# kijek_d1.net
KiCad netlist of a schematic drawn in Altium Designer
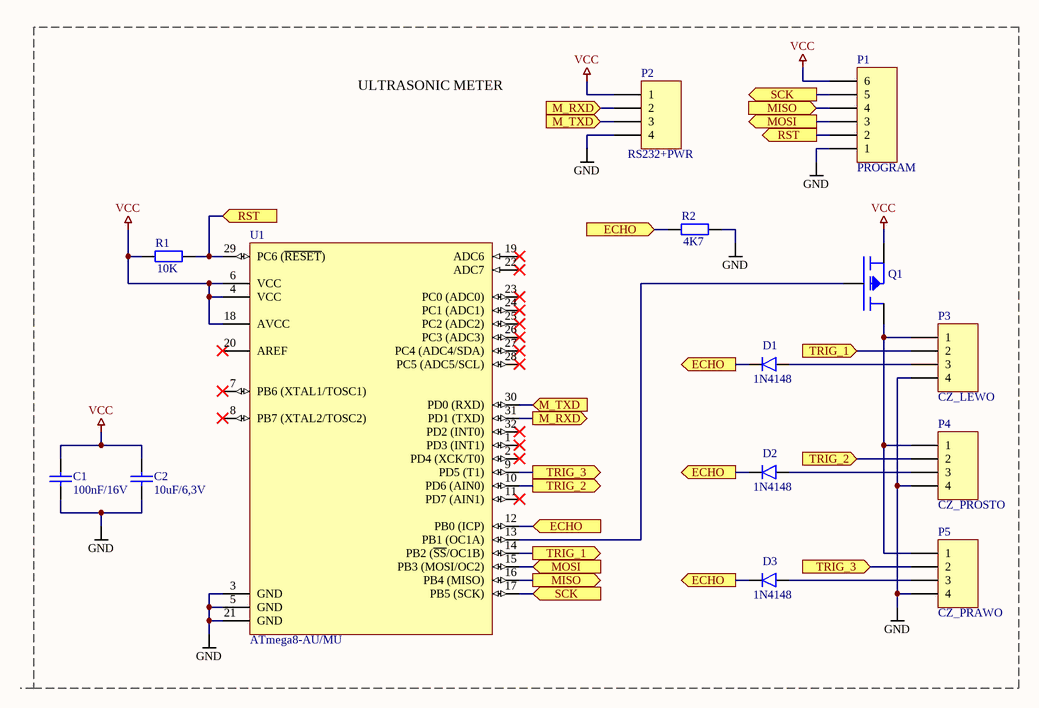
[diagram p0: kijek_d1.SchDoc]

(export (version "E")
  (design (tool "Eeschema 10.0.6"))
  (components
    (comp (ref "C1")
      (value "100nF/16V")
      (footprint "C0402")
      (description "Capacitor")
      (libsource (lib "Library") (part "Cap"))
    )
    (comp (ref "C2")
      (value "10uF/6,3V")
      (footprint "C0603")
      (description "Capacitor")
      (libsource (lib "Library") (part "Cap"))
    )
    (comp (ref "D1") (value "1N4148") (footprint "DO-213A") (libsource (lib "Library") (part "Diode")))
    (comp (ref "D2") (value "1N4148") (footprint "DO-213A") (libsource (lib "Library") (part "Diode")))
    (comp (ref "D3") (value "1N4148") (footprint "DO-213A") (libsource (lib "Library") (part "Diode")))
    (comp (ref "P1")
      (value "PROGRAM")
      (footprint "SMA06-1")
      (description "Header, 6-Pin")
      (libsource (lib "Connectors") (part "Header 6"))
    )
    (comp (ref "P2")
      (value "RS232+PWR")
      (footprint "MA04-1")
      (description "Header, 4-Pin")
      (libsource (lib "Connectors") (part "Header 4"))
    )
    (comp (ref "P3")
      (value "CZ_LEWO")
      (footprint "MA04-1")
      (description "Header, 4-Pin")
      (libsource (lib "Connectors") (part "Header 4"))
    )
    (comp (ref "P4")
      (value "CZ_PROSTO")
      (footprint "MA04-1")
      (description "Header, 4-Pin")
      (libsource (lib "Connectors") (part "Header 4"))
    )
    (comp (ref "P5")
      (value "CZ_PRAWO")
      (footprint "MA04-1")
      (description "Header, 4-Pin")
      (libsource (lib "Connectors") (part "Header 4"))
    )
    (comp (ref "Q1") (value "AO3401") (footprint "SOT23") (libsource (lib "Library") (part "AO3401")))
    (comp (ref "R1")
      (value "10K")
      (footprint "R0402")
      (description "Resistor")
      (libsource (lib "Library") (part "Res"))
    )
    (comp (ref "R2")
      (value "4K7")
      (footprint "R0402")
      (description "Resistor")
      (libsource (lib "Library") (part "Res"))
    )
    (comp (ref "U1")
      (value "ATmega8-AU/MU")
      (footprint "TQFP-32A")
      (description "TQFP - 32pin / MLF - 32pin")
      (libsource (lib "IC") (part "ATmega8-AU/MU"))
    )
  )
  (nets
    (net (code "1") (name "/ECHO") (class "Default")
      (node (ref "D1") (pin "1") (pinfunction "1_1") (pintype "power_in"))
      (node (ref "D2") (pin "1") (pinfunction "1_1") (pintype "power_in"))
      (node (ref "D3") (pin "1") (pinfunction "1_1") (pintype "power_in"))
      (node (ref "R2") (pin "1") (pinfunction "1_1") (pintype "passive"))
      (node (ref "U1") (pin "12") (pinfunction "PB0_(ICP)_12") (pintype "bidirectional"))
    )
    (net (code "2") (name "/MISO") (class "Default")
      (node (ref "P1") (pin "4") (pinfunction "4_4") (pintype "passive"))
      (node (ref "U1") (pin "16") (pinfunction "PB4_(MISO)_16") (pintype "bidirectional"))
    )
    (net (code "3") (name "/MOSI") (class "Default")
      (node (ref "P1") (pin "3") (pinfunction "3_3") (pintype "passive"))
      (node (ref "U1") (pin "15") (pinfunction "PB3_(MOSI/OC2)_15") (pintype "bidirectional"))
    )
    (net (code "4") (name "/M_RXD") (class "Default")
      (node (ref "P2") (pin "2") (pinfunction "2_2") (pintype "passive"))
      (node (ref "U1") (pin "31") (pinfunction "PD1_(TXD)_31") (pintype "bidirectional"))
    )
    (net (code "5") (name "/M_TXD") (class "Default")
      (node (ref "P2") (pin "3") (pinfunction "3_3") (pintype "passive"))
      (node (ref "U1") (pin "30") (pinfunction "PD0_(RXD)_30") (pintype "bidirectional"))
    )
    (net (code "6") (name "/RST") (class "Default")
      (node (ref "P1") (pin "2") (pinfunction "2_2") (pintype "passive"))
      (node (ref "R1") (pin "2") (pinfunction "2_2") (pintype "passive"))
      (node (ref "U1") (pin "29") (pinfunction "PC6_(~{RESET})_29") (pintype "bidirectional"))
    )
    (net (code "7") (name "/SCK") (class "Default")
      (node (ref "P1") (pin "5") (pinfunction "5_5") (pintype "passive"))
      (node (ref "U1") (pin "17") (pinfunction "PB5_(SCK)_17") (pintype "bidirectional"))
    )
    (net (code "8") (name "/TRIG_1") (class "Default")
      (node (ref "P3") (pin "2") (pinfunction "2_2") (pintype "passive"))
      (node (ref "U1") (pin "14") (pinfunction "PB2_(~{SS}/OC1B)_14") (pintype "bidirectional"))
    )
    (net (code "9") (name "/TRIG_2") (class "Default")
      (node (ref "P4") (pin "2") (pinfunction "2_2") (pintype "passive"))
      (node (ref "U1") (pin "10") (pinfunction "PD6_(AIN0)_10") (pintype "bidirectional"))
    )
    (net (code "10") (name "/TRIG_3") (class "Default")
      (node (ref "P5") (pin "2") (pinfunction "2_2") (pintype "passive"))
      (node (ref "U1") (pin "9") (pinfunction "PD5_(T1)_9") (pintype "bidirectional"))
    )
    (net (code "11") (name "GND") (class "Default")
      (node (ref "C1") (pin "2") (pinfunction "2_2") (pintype "passive"))
      (node (ref "C2") (pin "2") (pinfunction "2_2") (pintype "passive"))
      (node (ref "P1") (pin "1") (pinfunction "1_1") (pintype "passive"))
      (node (ref "P2") (pin "4") (pinfunction "4_4") (pintype "passive"))
      (node (ref "P3") (pin "4") (pinfunction "4_4") (pintype "passive"))
      (node (ref "P4") (pin "4") (pinfunction "4_4") (pintype "passive"))
      (node (ref "P5") (pin "4") (pinfunction "4_4") (pintype "passive"))
      (node (ref "R2") (pin "2") (pinfunction "2_2") (pintype "passive"))
      (node (ref "U1") (pin "21") (pinfunction "GND_21") (pintype "power_in"))
      (node (ref "U1") (pin "3") (pinfunction "GND_3") (pintype "power_in"))
      (node (ref "U1") (pin "5") (pinfunction "GND_5") (pintype "power_in"))
    )
    (net (code "12") (name "Net-(D1-Pad2)") (class "Default")
      (node (ref "D1") (pin "2") (pinfunction "2_2") (pintype "power_in"))
      (node (ref "P3") (pin "3") (pinfunction "3_3") (pintype "passive"))
    )
    (net (code "13") (name "Net-(D2-Pad2)") (class "Default")
      (node (ref "D2") (pin "2") (pinfunction "2_2") (pintype "power_in"))
      (node (ref "P4") (pin "3") (pinfunction "3_3") (pintype "passive"))
    )
    (net (code "14") (name "Net-(D3-Pad2)") (class "Default")
      (node (ref "D3") (pin "2") (pinfunction "2_2") (pintype "power_in"))
      (node (ref "P5") (pin "3") (pinfunction "3_3") (pintype "passive"))
    )
    (net (code "15") (name "Net-(Q1-D)") (class "Default")
      (node (ref "P3") (pin "1") (pinfunction "1_1") (pintype "passive"))
      (node (ref "P4") (pin "1") (pinfunction "1_1") (pintype "passive"))
      (node (ref "P5") (pin "1") (pinfunction "1_1") (pintype "passive"))
      (node (ref "Q1") (pin "3") (pinfunction "D_3") (pintype "passive"))
    )
    (net (code "16") (name "Net-(Q1-G)") (class "Default")
      (node (ref "Q1") (pin "1") (pinfunction "G_1") (pintype "passive"))
      (node (ref "U1") (pin "13") (pinfunction "PB1_(OC1A)_13") (pintype "bidirectional"))
    )
    (net (code "17") (name "VCC") (class "Default")
      (node (ref "C1") (pin "1") (pinfunction "1_1") (pintype "passive"))
      (node (ref "C2") (pin "1") (pinfunction "1_1") (pintype "passive"))
      (node (ref "P1") (pin "6") (pinfunction "6_6") (pintype "passive"))
      (node (ref "P2") (pin "1") (pinfunction "1_1") (pintype "passive"))
      (node (ref "Q1") (pin "2") (pinfunction "S_2") (pintype "passive"))
      (node (ref "R1") (pin "1") (pinfunction "1_1") (pintype "passive"))
      (node (ref "U1") (pin "18") (pinfunction "AVCC_18") (pintype "power_in"))
      (node (ref "U1") (pin "4") (pinfunction "VCC_4") (pintype "power_in"))
      (node (ref "U1") (pin "6") (pinfunction "VCC_6") (pintype "power_in"))
    )
    (net (code "18") (name "unconnected-(U1-ADC6-Pad19)") (class "Default")
      (node (ref "U1") (pin "19") (pinfunction "ADC6_19") (pintype "input+no_connect"))
    )
    (net (code "19") (name "unconnected-(U1-ADC7-Pad22)") (class "Default")
      (node (ref "U1") (pin "22") (pinfunction "ADC7_22") (pintype "input+no_connect"))
    )
    (net (code "20") (name "unconnected-(U1-AREF-Pad20)") (class "Default")
      (node (ref "U1") (pin "20") (pinfunction "AREF_20") (pintype "passive+no_connect"))
    )
    (net (code "21") (name "unconnected-(U1-PB6_(XTAL1{slash}TOSC1)-Pad7)") (class "Default")
      (node (ref "U1") (pin "7") (pinfunction "PB6_(XTAL1/TOSC1)_7") (pintype "bidirectional+no_connect"))
    )
    (net (code "22") (name "unconnected-(U1-PB7_(XTAL2{slash}TOSC2)-Pad8)") (class "Default")
      (node (ref "U1") (pin "8") (pinfunction "PB7_(XTAL2/TOSC2)_8") (pintype "bidirectional+no_connect"))
    )
    (net (code "23") (name "unconnected-(U1-PC0_(ADC0)-Pad23)") (class "Default")
      (node (ref "U1") (pin "23") (pinfunction "PC0_(ADC0)_23") (pintype "bidirectional+no_connect"))
    )
    (net (code "24") (name "unconnected-(U1-PC1_(ADC1)-Pad24)") (class "Default")
      (node (ref "U1") (pin "24") (pinfunction "PC1_(ADC1)_24") (pintype "bidirectional+no_connect"))
    )
    (net (code "25") (name "unconnected-(U1-PC2_(ADC2)-Pad25)") (class "Default")
      (node (ref "U1") (pin "25") (pinfunction "PC2_(ADC2)_25") (pintype "bidirectional+no_connect"))
    )
    (net (code "26") (name "unconnected-(U1-PC3_(ADC3)-Pad26)") (class "Default")
      (node (ref "U1") (pin "26") (pinfunction "PC3_(ADC3)_26") (pintype "bidirectional+no_connect"))
    )
    (net (code "27") (name "unconnected-(U1-PC4_(ADC4{slash}SDA)-Pad27)") (class "Default")
      (node (ref "U1") (pin "27") (pinfunction "PC4_(ADC4/SDA)_27") (pintype "bidirectional+no_connect"))
    )
    (net (code "28") (name "unconnected-(U1-PC5_(ADC5{slash}SCL)-Pad28)") (class "Default")
      (node (ref "U1") (pin "28") (pinfunction "PC5_(ADC5/SCL)_28") (pintype "bidirectional+no_connect"))
    )
    (net (code "29") (name "unconnected-(U1-PD2_(INT0)-Pad32)") (class "Default")
      (node (ref "U1") (pin "32") (pinfunction "PD2_(INT0)_32") (pintype "bidirectional+no_connect"))
    )
    (net (code "30") (name "unconnected-(U1-PD3_(INT1)-Pad1)") (class "Default")
      (node (ref "U1") (pin "1") (pinfunction "PD3_(INT1)_1") (pintype "bidirectional+no_connect"))
    )
    (net (code "31") (name "unconnected-(U1-PD4_(XCK{slash}T0)-Pad2)") (class "Default")
      (node (ref "U1") (pin "2") (pinfunction "PD4_(XCK/T0)_2") (pintype "bidirectional+no_connect"))
    )
    (net (code "32") (name "unconnected-(U1-PD7_(AIN1)-Pad11)") (class "Default")
      (node (ref "U1") (pin "11") (pinfunction "PD7_(AIN1)_11") (pintype "bidirectional+no_connect"))
    )
  )
)
